# CON_PCIe_X4.net
KiCad netlist of a schematic drawn in Altium Designer
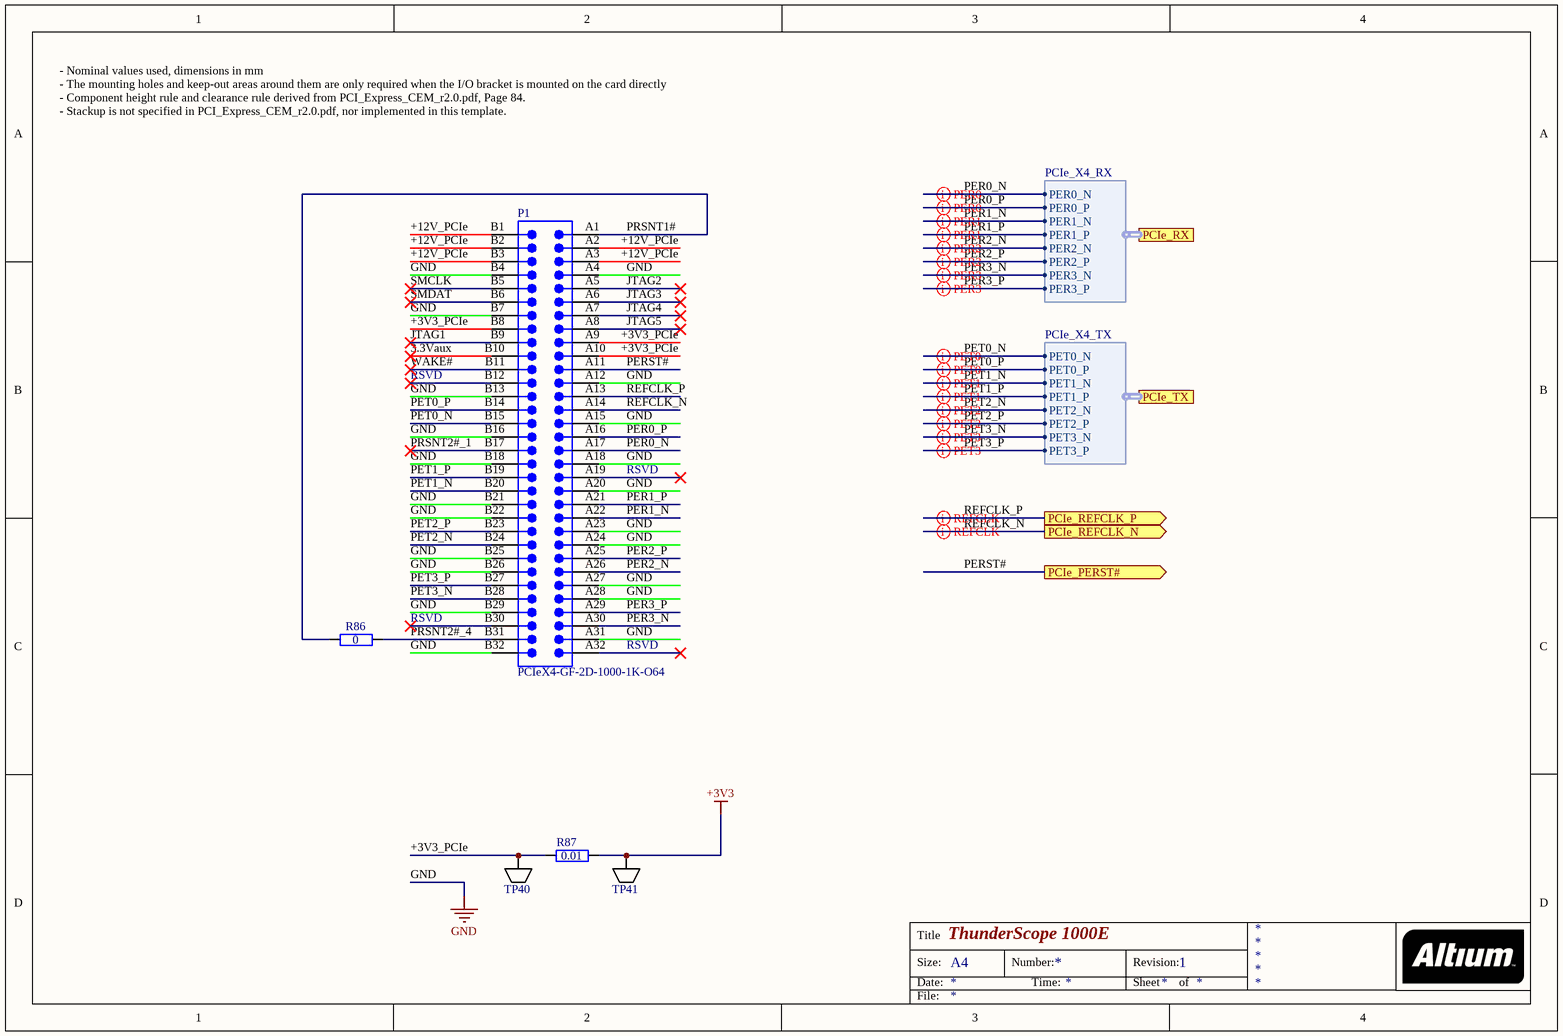
[diagram p0: CON_PCIe_X4.SchDoc]

(export (version "E")
  (design (tool "Eeschema 10.0.6"))
  (components
    (comp (ref "P1")
      (value "PCIeX4-GF-2D-1000-1K-O64")
      (footprint "PCIeX4-GF-2D-1000-1K-O64")
      (description "Golden finger, PCIeX4, Dual, Opposite, Pitch 1mm, 64-Position")
      (fields (field (name "PUBLISHER") "Altium"))
      (libsource (lib "Altium Content Vault") (part "PCIeX4-GF-2D-1000-1K-O64"))
    )
    (comp (ref "R86")
      (value "0")
      (footprint "GEN_R_0402")
      (libsource (lib "DSO") (part "RES 0 OHM 1/16W 0402"))
    )
    (comp (ref "R87")
      (value "0.01")
      (footprint "GEN_R_0603")
      (fields (field (name "TOLERANCE") "1%"))
      (libsource (lib "DSO") (part "RES 0.01 OHM 1% 1/4W 0603"))
    )
    (comp (ref "TP40")
      (value "5015")
      (footprint "KEY_5015")
      (libsource (lib "DSO") (part "TP KEYSTONE 5015"))
    )
    (comp (ref "TP41")
      (value "5015")
      (footprint "KEY_5015")
      (libsource (lib "DSO") (part "TP KEYSTONE 5015"))
    )
  )
  (nets
    (net (code "3") (name "+3V3") (class "Default")
      (node (ref "R87") (pin "2") (pinfunction "2_2") (pintype "passive"))
      (node (ref "TP41") (pin "1") (pinfunction "1_1") (pintype "passive"))
    )
    (net (code "4") (name "/+3V3_PCIe") (class "Default")
      (node (ref "P1") (pin "A10") (pinfunction "A10_A10") (pintype "passive"))
      (node (ref "P1") (pin "A9") (pinfunction "A9_A9") (pintype "passive"))
      (node (ref "P1") (pin "B8") (pinfunction "B8_B8") (pintype "passive"))
      (node (ref "R87") (pin "1") (pinfunction "1_1") (pintype "passive"))
      (node (ref "TP40") (pin "1") (pinfunction "1_1") (pintype "passive"))
    )
    (net (code "5") (name "/+12V_PCIe") (class "Default")
      (node (ref "P1") (pin "A2") (pinfunction "A2_A2") (pintype "passive"))
      (node (ref "P1") (pin "A3") (pinfunction "A3_A3") (pintype "passive"))
      (node (ref "P1") (pin "B1") (pinfunction "B1_B1") (pintype "passive"))
      (node (ref "P1") (pin "B2") (pinfunction "B2_B2") (pintype "passive"))
      (node (ref "P1") (pin "B3") (pinfunction "B3_B3") (pintype "passive"))
    )
    (net (code "6") (name "/3.3Vaux") (class "Default")
      (node (ref "P1") (pin "B10") (pinfunction "B10_B10") (pintype "passive+no_connect"))
    )
    (net (code "7") (name "/JTAG1") (class "Default")
      (node (ref "P1") (pin "B9") (pinfunction "B9_B9") (pintype "passive+no_connect"))
    )
    (net (code "8") (name "/JTAG2") (class "Default")
      (node (ref "P1") (pin "A5") (pinfunction "A5_A5") (pintype "passive+no_connect"))
    )
    (net (code "9") (name "/JTAG3") (class "Default")
      (node (ref "P1") (pin "A6") (pinfunction "A6_A6") (pintype "passive+no_connect"))
    )
    (net (code "10") (name "/JTAG4") (class "Default")
      (node (ref "P1") (pin "A7") (pinfunction "A7_A7") (pintype "passive+no_connect"))
    )
    (net (code "11") (name "/JTAG5") (class "Default")
      (node (ref "P1") (pin "A8") (pinfunction "A8_A8") (pintype "passive+no_connect"))
    )
    (net (code "12") (name "/PER0_N") (class "Default")
      (node (ref "P1") (pin "A17") (pinfunction "A17_A17") (pintype "passive"))
    )
    (net (code "13") (name "/PER0_P") (class "Default")
      (node (ref "P1") (pin "A16") (pinfunction "A16_A16") (pintype "passive"))
    )
    (net (code "14") (name "/PER1_N") (class "Default")
      (node (ref "P1") (pin "A22") (pinfunction "A22_A22") (pintype "passive"))
    )
    (net (code "15") (name "/PER1_P") (class "Default")
      (node (ref "P1") (pin "A21") (pinfunction "A21_A21") (pintype "passive"))
    )
    (net (code "16") (name "/PER2_N") (class "Default")
      (node (ref "P1") (pin "A26") (pinfunction "A26_A26") (pintype "passive"))
    )
    (net (code "17") (name "/PER2_P") (class "Default")
      (node (ref "P1") (pin "A25") (pinfunction "A25_A25") (pintype "passive"))
    )
    (net (code "18") (name "/PER3_N") (class "Default")
      (node (ref "P1") (pin "A30") (pinfunction "A30_A30") (pintype "passive"))
    )
    (net (code "19") (name "/PER3_P") (class "Default")
      (node (ref "P1") (pin "A29") (pinfunction "A29_A29") (pintype "passive"))
    )
    (net (code "20") (name "/PERST#") (class "Default")
      (node (ref "P1") (pin "A11") (pinfunction "A11_A11") (pintype "passive"))
    )
    (net (code "21") (name "/PET0_N") (class "Default")
      (node (ref "P1") (pin "B15") (pinfunction "B15_B15") (pintype "passive"))
    )
    (net (code "22") (name "/PET0_P") (class "Default")
      (node (ref "P1") (pin "B14") (pinfunction "B14_B14") (pintype "passive"))
    )
    (net (code "23") (name "/PET1_N") (class "Default")
      (node (ref "P1") (pin "B20") (pinfunction "B20_B20") (pintype "passive"))
    )
    (net (code "24") (name "/PET1_P") (class "Default")
      (node (ref "P1") (pin "B19") (pinfunction "B19_B19") (pintype "passive"))
    )
    (net (code "25") (name "/PET2_N") (class "Default")
      (node (ref "P1") (pin "B24") (pinfunction "B24_B24") (pintype "passive"))
    )
    (net (code "26") (name "/PET2_P") (class "Default")
      (node (ref "P1") (pin "B23") (pinfunction "B23_B23") (pintype "passive"))
    )
    (net (code "27") (name "/PET3_N") (class "Default")
      (node (ref "P1") (pin "B28") (pinfunction "B28_B28") (pintype "passive"))
    )
    (net (code "28") (name "/PET3_P") (class "Default")
      (node (ref "P1") (pin "B27") (pinfunction "B27_B27") (pintype "passive"))
    )
    (net (code "29") (name "/PRSNT1#") (class "Default")
      (node (ref "P1") (pin "A1") (pinfunction "A1_A1") (pintype "passive"))
      (node (ref "R86") (pin "1") (pinfunction "1_1") (pintype "passive"))
    )
    (net (code "30") (name "/PRSNT2#_1") (class "Default")
      (node (ref "P1") (pin "B17") (pinfunction "B17_B17") (pintype "passive+no_connect"))
    )
    (net (code "31") (name "/PRSNT2#_4") (class "Default")
      (node (ref "P1") (pin "B31") (pinfunction "B31_B31") (pintype "passive"))
      (node (ref "R86") (pin "2") (pinfunction "2_2") (pintype "passive"))
    )
    (net (code "32") (name "/REFCLK_N") (class "Default")
      (node (ref "P1") (pin "A14") (pinfunction "A14_A14") (pintype "passive"))
    )
    (net (code "33") (name "/REFCLK_P") (class "Default")
      (node (ref "P1") (pin "A13") (pinfunction "A13_A13") (pintype "passive"))
    )
    (net (code "34") (name "/SMCLK") (class "Default")
      (node (ref "P1") (pin "B5") (pinfunction "B5_B5") (pintype "passive+no_connect"))
    )
    (net (code "35") (name "/SMDAT") (class "Default")
      (node (ref "P1") (pin "B6") (pinfunction "B6_B6") (pintype "passive+no_connect"))
    )
    (net (code "36") (name "/WAKE#") (class "Default")
      (node (ref "P1") (pin "B11") (pinfunction "B11_B11") (pintype "passive+no_connect"))
    )
    (net (code "39") (name "GND") (class "Default")
      (node (ref "P1") (pin "A12") (pinfunction "A12_A12") (pintype "passive"))
      (node (ref "P1") (pin "A15") (pinfunction "A15_A15") (pintype "passive"))
      (node (ref "P1") (pin "A18") (pinfunction "A18_A18") (pintype "passive"))
      (node (ref "P1") (pin "A20") (pinfunction "A20_A20") (pintype "passive"))
      (node (ref "P1") (pin "A23") (pinfunction "A23_A23") (pintype "passive"))
      (node (ref "P1") (pin "A24") (pinfunction "A24_A24") (pintype "passive"))
      (node (ref "P1") (pin "A27") (pinfunction "A27_A27") (pintype "passive"))
      (node (ref "P1") (pin "A28") (pinfunction "A28_A28") (pintype "passive"))
      (node (ref "P1") (pin "A31") (pinfunction "A31_A31") (pintype "passive"))
      (node (ref "P1") (pin "A4") (pinfunction "A4_A4") (pintype "passive"))
      (node (ref "P1") (pin "B13") (pinfunction "B13_B13") (pintype "passive"))
      (node (ref "P1") (pin "B16") (pinfunction "B16_B16") (pintype "passive"))
      (node (ref "P1") (pin "B18") (pinfunction "B18_B18") (pintype "passive"))
      (node (ref "P1") (pin "B21") (pinfunction "B21_B21") (pintype "passive"))
      (node (ref "P1") (pin "B22") (pinfunction "B22_B22") (pintype "passive"))
      (node (ref "P1") (pin "B25") (pinfunction "B25_B25") (pintype "passive"))
      (node (ref "P1") (pin "B26") (pinfunction "B26_B26") (pintype "passive"))
      (node (ref "P1") (pin "B29") (pinfunction "B29_B29") (pintype "passive"))
      (node (ref "P1") (pin "B32") (pinfunction "B32_B32") (pintype "passive"))
      (node (ref "P1") (pin "B4") (pinfunction "B4_B4") (pintype "passive"))
      (node (ref "P1") (pin "B7") (pinfunction "B7_B7") (pintype "passive"))
    )
    (net (code "40") (name "unconnected-(P1-PadA19)") (class "Default")
      (node (ref "P1") (pin "A19") (pinfunction "A19_A19") (pintype "passive+no_connect"))
    )
    (net (code "41") (name "unconnected-(P1-PadA32)") (class "Default")
      (node (ref "P1") (pin "A32") (pinfunction "A32_A32") (pintype "passive+no_connect"))
    )
    (net (code "42") (name "unconnected-(P1-PadB12)") (class "Default")
      (node (ref "P1") (pin "B12") (pinfunction "B12_B12") (pintype "passive+no_connect"))
    )
    (net (code "43") (name "unconnected-(P1-PadB30)") (class "Default")
      (node (ref "P1") (pin "B30") (pinfunction "B30_B30") (pintype "passive+no_connect"))
    )
  )
)
